# SCHEMATIC.net
KiCad netlist of a schematic drawn in EasyEDA
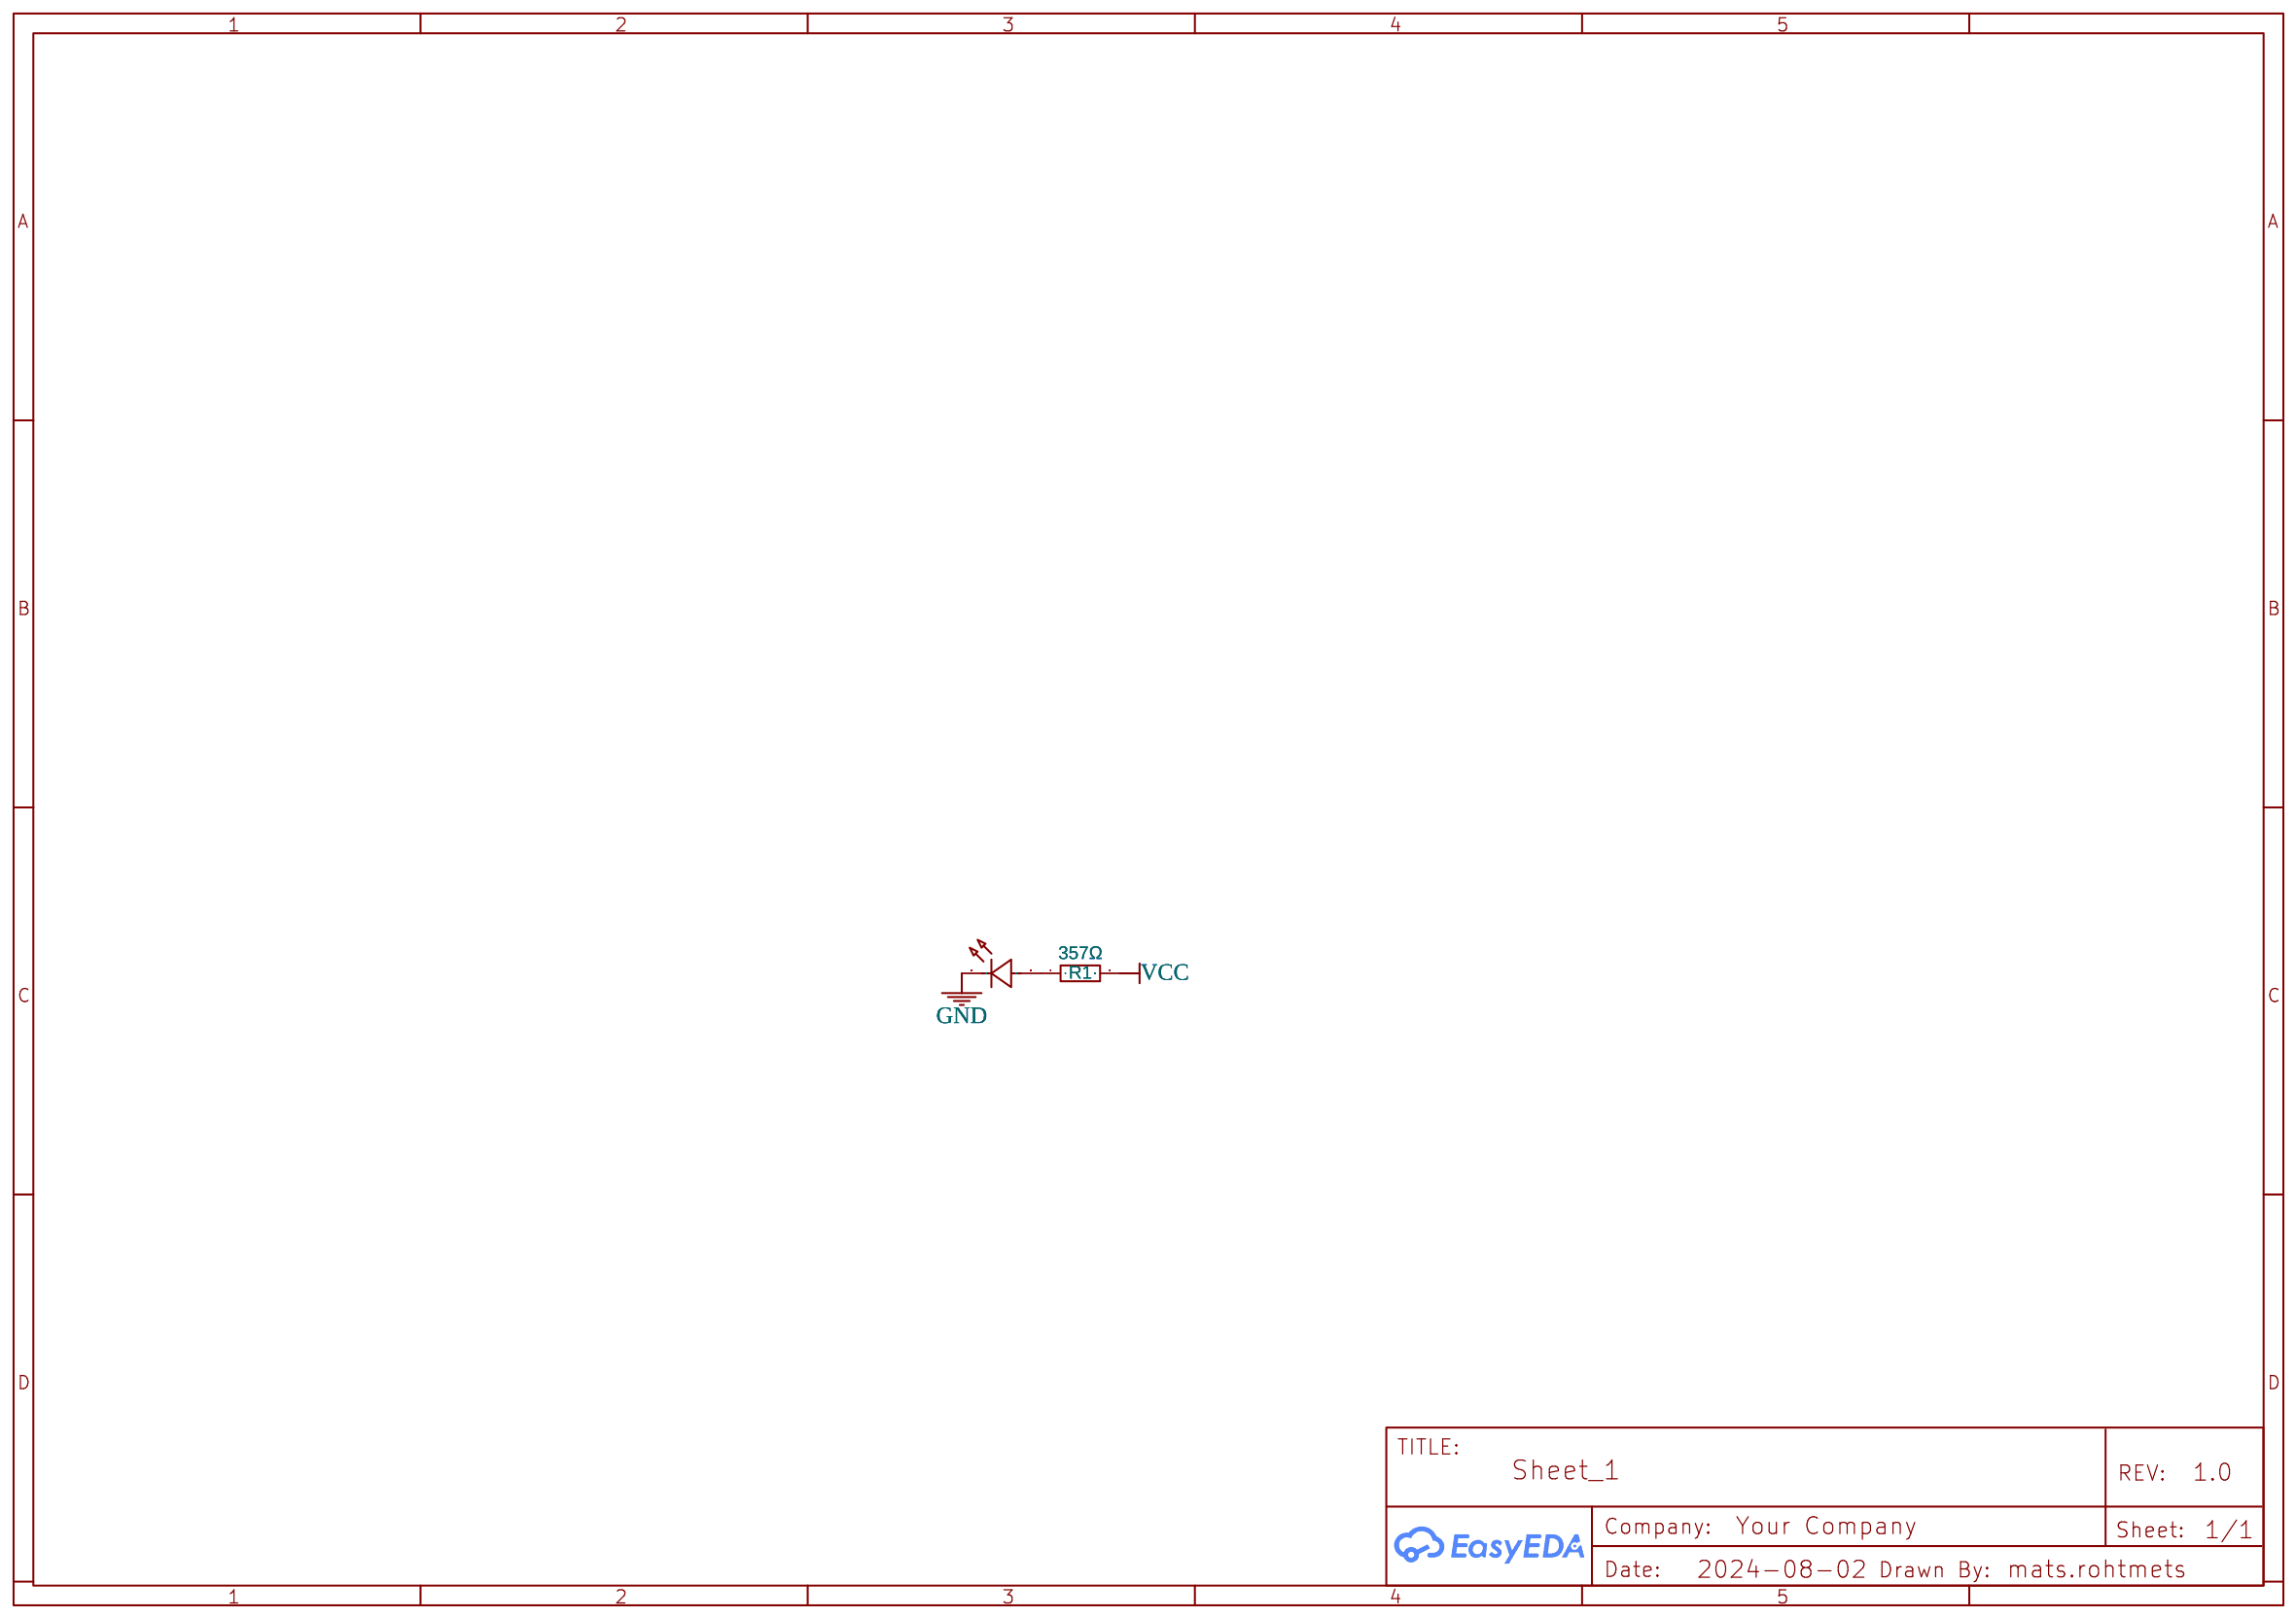
[diagram p0: schematic sheet]

(export (version "E")
  (design (tool "Eeschema 10.0.6"))
  (components
    (comp (ref "L1")
      (value "XL-3216UYC_C965824")
      (fields (field (name "Manufacturer Part") "XL-3216UYC") (field (name "Manufacturer") "XINGLIGHT(成兴光)"))
      (libsource (lib "") (part "XL-3216UYC_C965824"))
    )
    (comp (ref "R1")
      (value "357Ω")
      (fields (field (name "Manufacturer Part") "ARG05FTC3570") (field (name "Manufacturer") "Viking(光颉)"))
      (libsource (lib "") (part "ARG05FTC3570"))
    )
  )
  (nets
    (net (code "1") (name "GND") (class "Default")
      (node (ref "L1") (pin "1") (pinfunction "K_1") (pintype "unspecified"))
    )
    (net (code "2") (name "Net-(L1-A)") (class "Default")
      (node (ref "L1") (pin "2") (pinfunction "A_2") (pintype "unspecified"))
      (node (ref "R1") (pin "1") (pinfunction "1_1") (pintype "unspecified"))
    )
    (net (code "3") (name "VCC") (class "Default")
      (node (ref "R1") (pin "2") (pinfunction "2_2") (pintype "unspecified"))
    )
  )
)
